# beaconboard3.net
KiCad netlist of a schematic drawn in EAGLE
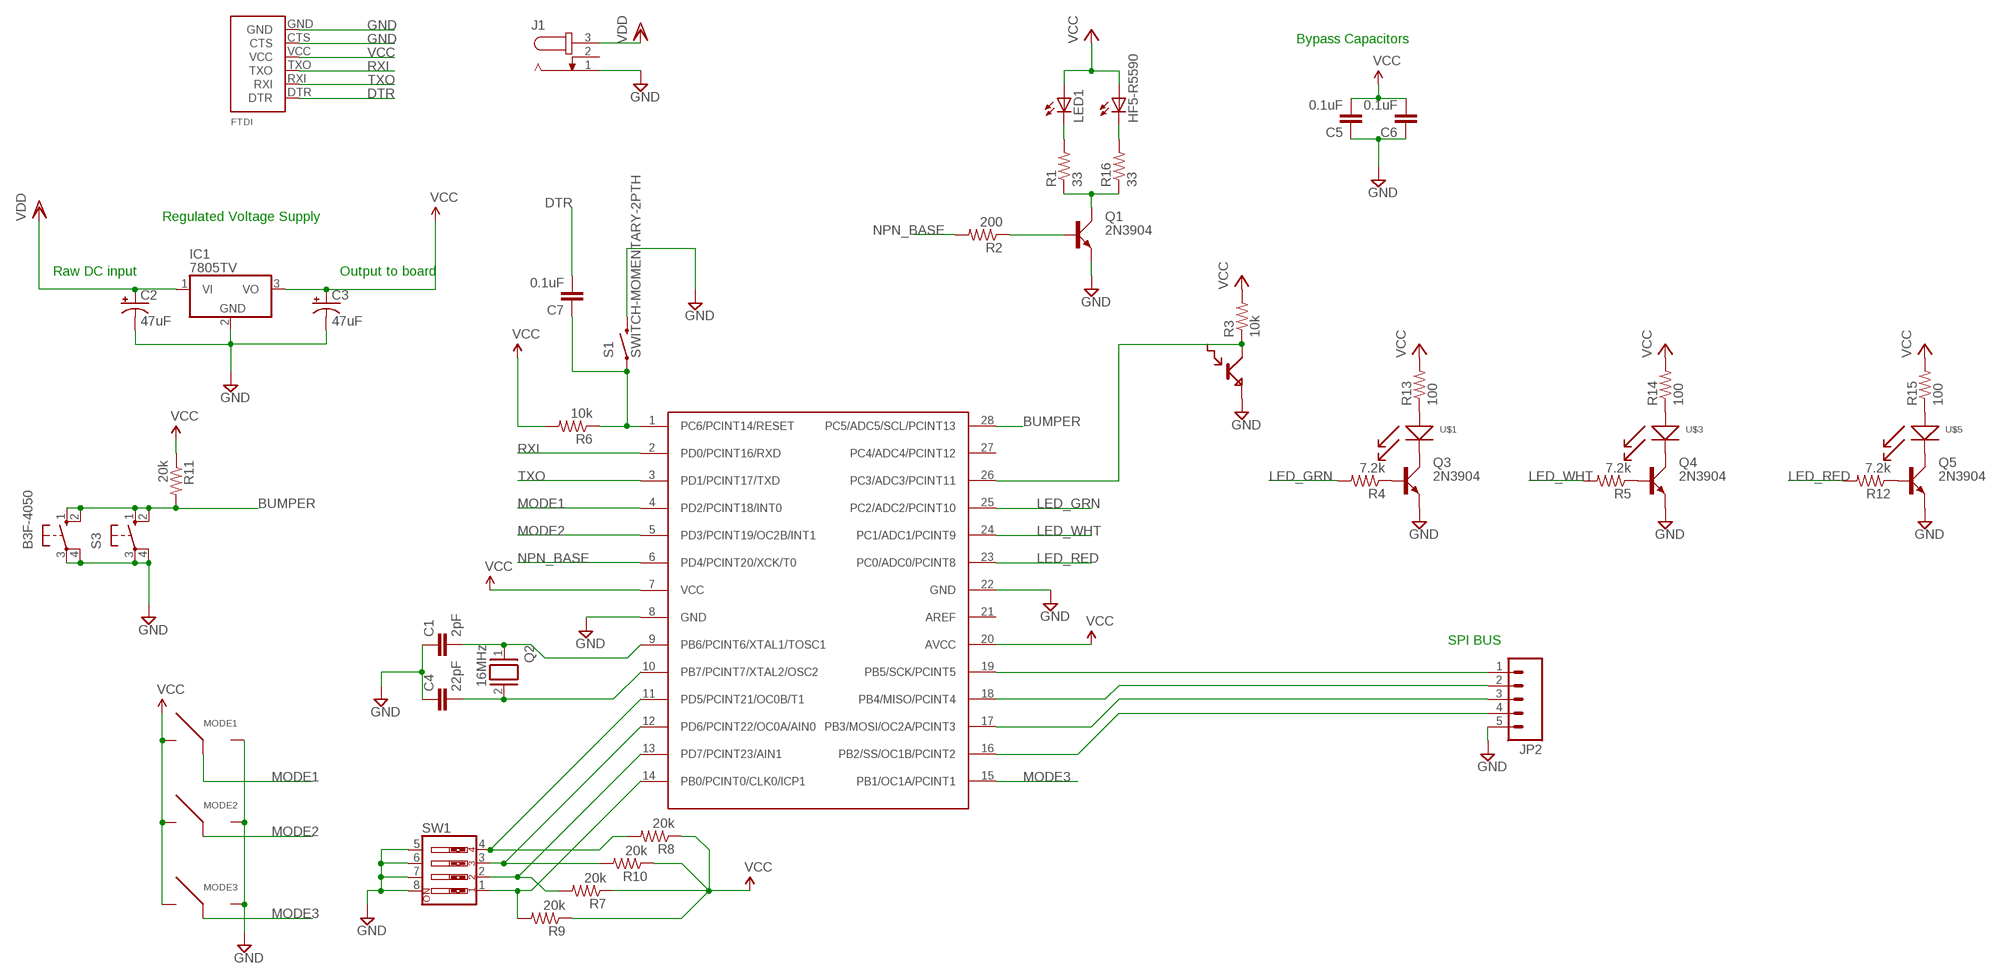
[diagram p0: schematic, sheet 1]

(export (version "E")
  (design (tool "Eeschema 10.0.6"))
  (components
    (comp (ref "B3F-4050")
      (value "40-XX")
      (footprint "eagle-import:B3F-40XX")
      (fields (field (name "MF") "OMRON COMPONENTS USA") (field (name "MPN") "B3F-4000"))
      (libsource (lib "eagle-import") (part "40-XX"))
    )
    (comp (ref "C1")
      (value "2pF")
      (footprint "eagle-import:CAP-PTH-SMALL")
      (libsource (lib "eagle-import") (part "CAPPTH"))
    )
    (comp (ref "C2")
      (value "47uF")
      (footprint "eagle-import:CPOL-RADIAL-10UF-25V")
      (libsource (lib "eagle-import") (part "CAP_POLPTH2"))
    )
    (comp (ref "C3")
      (value "47uF")
      (footprint "eagle-import:CPOL-RADIAL-10UF-25V")
      (libsource (lib "eagle-import") (part "CAP_POLPTH2"))
    )
    (comp (ref "C4")
      (value "22pF")
      (footprint "eagle-import:CAP-PTH-SMALL")
      (libsource (lib "eagle-import") (part "CAPPTH"))
    )
    (comp (ref "C5")
      (value "0.1uF")
      (footprint "eagle-import:CAP-PTH-5MM")
      (libsource (lib "eagle-import") (part "CAPPTH1"))
    )
    (comp (ref "C6")
      (value "0.1uF")
      (footprint "eagle-import:CAP-PTH-5MM")
      (libsource (lib "eagle-import") (part "CAPPTH1"))
    )
    (comp (ref "C7")
      (value "0.1uF")
      (footprint "eagle-import:CAP-PTH-5MM")
      (libsource (lib "eagle-import") (part "CAPPTH1"))
    )
    (comp (ref "HF5-R5590")
      (value "LED-2AC-CP41B-WES")
      (footprint "eagle-import:CP41B")
      (libsource (lib "eagle-import") (part "LED-2AC-CP41B-WES"))
    )
    (comp (ref "IC1")
      (value "7805TV")
      (footprint "eagle-import:TO220V")
      (libsource (lib "eagle-import") (part "78TV05"))
    )
    (comp (ref "J1")
      (value "JACK-PLUG1")
      (footprint "eagle-import:SPC4078")
      (libsource (lib "eagle-import") (part "JACK-PLUG1"))
    )
    (comp (ref "JP2")
      (value "M05LOCK_LONGPADS")
      (footprint "eagle-import:1X05_LOCK_LONGPADS")
      (libsource (lib "eagle-import") (part "M05LOCK_LONGPADS"))
    )
    (comp (ref "LED1")
      (value "LED-2AC-CP41B-WES")
      (footprint "eagle-import:CP41B")
      (libsource (lib "eagle-import") (part "LED-2AC-CP41B-WES"))
    )
    (comp (ref "MODE1")
      (value "SPD_SLIDE_SWITCH")
      (footprint "eagle-import:SPDT_SLIDE_SWITCH")
      (libsource (lib "eagle-import") (part "SPD_SLIDE_SWITCH"))
    )
    (comp (ref "MODE2")
      (value "SPD_SLIDE_SWITCH")
      (footprint "eagle-import:SPDT_SLIDE_SWITCH")
      (libsource (lib "eagle-import") (part "SPD_SLIDE_SWITCH"))
    )
    (comp (ref "MODE3")
      (value "SPD_SLIDE_SWITCH")
      (footprint "eagle-import:SPDT_SLIDE_SWITCH")
      (libsource (lib "eagle-import") (part "SPD_SLIDE_SWITCH"))
    )
    (comp (ref "Q1")
      (value "2N3904")
      (footprint "eagle-import:TO92D")
      (libsource (lib "eagle-import") (part "2N3904"))
    )
    (comp (ref "Q2")
      (value "16MHz")
      (footprint "eagle-import:QS")
      (libsource (lib "eagle-import") (part "XTAL/S"))
    )
    (comp (ref "Q3")
      (value "2N3904")
      (footprint "eagle-import:TO92D")
      (libsource (lib "eagle-import") (part "2N3904"))
    )
    (comp (ref "Q4")
      (value "2N3904")
      (footprint "eagle-import:TO92D")
      (libsource (lib "eagle-import") (part "2N3904"))
    )
    (comp (ref "Q5")
      (value "2N3904")
      (footprint "eagle-import:TO92D")
      (libsource (lib "eagle-import") (part "2N3904"))
    )
    (comp (ref "R1")
      (value "33")
      (footprint "eagle-import:AXIAL-0.4")
      (libsource (lib "eagle-import") (part "RESISTORPTH-1/4W"))
    )
    (comp (ref "R2")
      (value "200")
      (footprint "eagle-import:AXIAL-0.4")
      (libsource (lib "eagle-import") (part "RESISTORPTH-1/4W"))
    )
    (comp (ref "R3")
      (value "10k")
      (footprint "eagle-import:AXIAL-0.4")
      (libsource (lib "eagle-import") (part "RESISTORPTH-1/4W"))
    )
    (comp (ref "R4")
      (value "7.2k")
      (footprint "eagle-import:AXIAL-0.4")
      (libsource (lib "eagle-import") (part "RESISTORPTH-1/4W"))
    )
    (comp (ref "R5")
      (value "7.2k")
      (footprint "eagle-import:AXIAL-0.4")
      (libsource (lib "eagle-import") (part "RESISTORPTH-1/4W"))
    )
    (comp (ref "R6")
      (value "10k")
      (footprint "eagle-import:AXIAL-0.4")
      (libsource (lib "eagle-import") (part "RESISTORPTH-1/4W"))
    )
    (comp (ref "R7")
      (value "20k")
      (footprint "eagle-import:AXIAL-0.4")
      (libsource (lib "eagle-import") (part "RESISTORPTH-1/4W"))
    )
    (comp (ref "R8")
      (value "20k")
      (footprint "eagle-import:AXIAL-0.4")
      (libsource (lib "eagle-import") (part "RESISTORPTH-1/4W"))
    )
    (comp (ref "R9")
      (value "20k")
      (footprint "eagle-import:AXIAL-0.4")
      (libsource (lib "eagle-import") (part "RESISTORPTH-1/4W"))
    )
    (comp (ref "R10")
      (value "20k")
      (footprint "eagle-import:AXIAL-0.4")
      (libsource (lib "eagle-import") (part "RESISTORPTH-1/4W"))
    )
    (comp (ref "R11")
      (value "20k")
      (footprint "eagle-import:AXIAL-0.4")
      (libsource (lib "eagle-import") (part "RESISTORPTH-1/4W"))
    )
    (comp (ref "R12")
      (value "7.2k")
      (footprint "eagle-import:AXIAL-0.4")
      (libsource (lib "eagle-import") (part "RESISTORPTH-1/4W"))
    )
    (comp (ref "R13")
      (value "100")
      (footprint "eagle-import:AXIAL-0.4")
      (libsource (lib "eagle-import") (part "RESISTORPTH-1/4W"))
    )
    (comp (ref "R14")
      (value "100")
      (footprint "eagle-import:AXIAL-0.4")
      (libsource (lib "eagle-import") (part "RESISTORPTH-1/4W"))
    )
    (comp (ref "R15")
      (value "100")
      (footprint "eagle-import:AXIAL-0.4")
      (libsource (lib "eagle-import") (part "RESISTORPTH-1/4W"))
    )
    (comp (ref "R16")
      (value "33")
      (footprint "eagle-import:AXIAL-0.4")
      (libsource (lib "eagle-import") (part "RESISTORPTH-1/4W"))
    )
    (comp (ref "S1")
      (value "SWITCH-MOMENTARY-2PTH")
      (footprint "eagle-import:TACTILE-PTH")
      (libsource (lib "eagle-import") (part "SWITCH-MOMENTARY-2PTH"))
    )
    (comp (ref "S3")
      (value "40-XX")
      (footprint "eagle-import:B3F-40XX")
      (fields (field (name "MF") "OMRON COMPONENTS USA") (field (name "MPN") "B3F-4000"))
      (libsource (lib "eagle-import") (part "40-XX"))
    )
    (comp (ref "SW1")
      (value "SW_DIP-4")
      (footprint "eagle-import:EDG-04")
      (libsource (lib "eagle-import") (part "SW_DIP-4"))
    )
    (comp (ref "U$1")
      (value "8MM_LED")
      (footprint "eagle-import:8MM_LED")
      (libsource (lib "eagle-import") (part "8MM_LED"))
    )
    (comp (ref "U$2")
      (value "BPW77NA")
      (footprint "eagle-import:TO-18")
      (libsource (lib "eagle-import") (part "BPW77NA"))
    )
    (comp (ref "U$3")
      (value "8MM_LED")
      (footprint "eagle-import:8MM_LED")
      (libsource (lib "eagle-import") (part "8MM_LED"))
    )
    (comp (ref "U$4")
      (value "ATMEGA328")
      (footprint "eagle-import:DIL28-3")
      (libsource (lib "eagle-import") (part "ATMEGA328"))
    )
    (comp (ref "U$5")
      (value "8MM_LED")
      (footprint "eagle-import:8MM_LED")
      (libsource (lib "eagle-import") (part "8MM_LED"))
    )
    (comp (ref "U$6")
      (value "FTDI")
      (footprint "eagle-import:FTDI")
      (libsource (lib "eagle-import") (part "FTDI"))
    )
  )
  (nets
    (net (code "1") (name "/BUMPER") (class "Default")
      (node (ref "B3F-4050") (pin "1") (pinfunction "S_1") (pintype "passive"))
      (node (ref "B3F-4050") (pin "2") (pinfunction "S1_2") (pintype "passive"))
      (node (ref "R11") (pin "P$2") (pinfunction "2_P$2") (pintype "passive"))
      (node (ref "S3") (pin "1") (pinfunction "S_1") (pintype "passive"))
      (node (ref "S3") (pin "2") (pinfunction "S1_2") (pintype "passive"))
      (node (ref "U$4") (pin "28") (pinfunction "PC5/ADC5/SCL/PCINT13_28") (pintype "bidirectional"))
    )
    (net (code "2") (name "/DTR") (class "Default")
      (node (ref "C7") (pin "2") (pinfunction "2_2") (pintype "passive"))
      (node (ref "U$6") (pin "DTR") (pinfunction "DTR_DTR") (pintype "bidirectional"))
    )
    (net (code "3") (name "/LED_GRN") (class "Default")
      (node (ref "R4") (pin "P$2") (pinfunction "2_P$2") (pintype "passive"))
      (node (ref "U$4") (pin "25") (pinfunction "PC2/ADC2/PCINT10_25") (pintype "bidirectional"))
    )
    (net (code "4") (name "/LED_RED") (class "Default")
      (node (ref "R12") (pin "P$2") (pinfunction "2_P$2") (pintype "passive"))
      (node (ref "U$4") (pin "23") (pinfunction "PC0/ADC0/PCINT8_23") (pintype "bidirectional"))
    )
    (net (code "5") (name "/LED_WHT") (class "Default")
      (node (ref "R5") (pin "P$2") (pinfunction "2_P$2") (pintype "passive"))
      (node (ref "U$4") (pin "24") (pinfunction "PC1/ADC1/PCINT9_24") (pintype "bidirectional"))
    )
    (net (code "6") (name "/MODE1") (class "Default")
      (node (ref "MODE1") (pin "2") (pinfunction "2_2") (pintype "bidirectional"))
      (node (ref "U$4") (pin "4") (pinfunction "PD2/PCINT18/INT0_4") (pintype "bidirectional"))
    )
    (net (code "7") (name "/MODE2") (class "Default")
      (node (ref "MODE2") (pin "2") (pinfunction "2_2") (pintype "bidirectional"))
      (node (ref "U$4") (pin "5") (pinfunction "PD3/PCINT19/OC2B/INT1_5") (pintype "bidirectional"))
    )
    (net (code "8") (name "/MODE3") (class "Default")
      (node (ref "MODE3") (pin "2") (pinfunction "2_2") (pintype "bidirectional"))
      (node (ref "U$4") (pin "15") (pinfunction "PB1/OC1A/PCINT1_15") (pintype "bidirectional"))
    )
    (net (code "9") (name "/NPN_BASE") (class "Default")
      (node (ref "R2") (pin "P$2") (pinfunction "2_P$2") (pintype "passive"))
      (node (ref "U$4") (pin "6") (pinfunction "PD4/PCINT20/XCK/T0_6") (pintype "bidirectional"))
    )
    (net (code "10") (name "/RXI") (class "Default")
      (node (ref "U$4") (pin "2") (pinfunction "PD0/PCINT16/RXD_2") (pintype "bidirectional"))
      (node (ref "U$6") (pin "TXO") (pinfunction "TXO_TXO") (pintype "bidirectional"))
    )
    (net (code "11") (name "/TXO") (class "Default")
      (node (ref "U$4") (pin "3") (pinfunction "PD1/PCINT17/TXD_3") (pintype "bidirectional"))
      (node (ref "U$6") (pin "RXI") (pinfunction "RXI_RXI") (pintype "bidirectional"))
    )
    (net (code "12") (name "GND") (class "Default")
      (node (ref "B3F-4050") (pin "3") (pinfunction "P_3") (pintype "passive"))
      (node (ref "B3F-4050") (pin "4") (pinfunction "P1_4") (pintype "passive"))
      (node (ref "C1") (pin "1") (pinfunction "1_1") (pintype "passive"))
      (node (ref "C2") (pin "2") (pinfunction "-_2") (pintype "passive"))
      (node (ref "C3") (pin "2") (pinfunction "-_2") (pintype "passive"))
      (node (ref "C4") (pin "1") (pinfunction "1_1") (pintype "passive"))
      (node (ref "C5") (pin "1") (pinfunction "1_1") (pintype "passive"))
      (node (ref "C6") (pin "1") (pinfunction "1_1") (pintype "passive"))
      (node (ref "IC1") (pin "2") (pinfunction "GND_2") (pintype "passive"))
      (node (ref "J1") (pin "1") (pinfunction "1_1") (pintype "passive"))
      (node (ref "JP2") (pin "5") (pinfunction "5_5") (pintype "passive"))
      (node (ref "MODE1") (pin "3") (pinfunction "3_3") (pintype "bidirectional"))
      (node (ref "MODE2") (pin "3") (pinfunction "3_3") (pintype "bidirectional"))
      (node (ref "MODE3") (pin "3") (pinfunction "3_3") (pintype "bidirectional"))
      (node (ref "Q1") (pin "E") (pinfunction "E_E") (pintype "passive"))
      (node (ref "Q3") (pin "E") (pinfunction "E_E") (pintype "passive"))
      (node (ref "Q4") (pin "E") (pinfunction "E_E") (pintype "passive"))
      (node (ref "Q5") (pin "E") (pinfunction "E_E") (pintype "passive"))
      (node (ref "S1") (pin "3") (pinfunction "2_3") (pintype "passive"))
      (node (ref "S3") (pin "3") (pinfunction "P_3") (pintype "passive"))
      (node (ref "S3") (pin "4") (pinfunction "P1_4") (pintype "passive"))
      (node (ref "SW1") (pin "5") (pinfunction "5_5") (pintype "passive"))
      (node (ref "SW1") (pin "6") (pinfunction "6_6") (pintype "passive"))
      (node (ref "SW1") (pin "7") (pinfunction "7_7") (pintype "passive"))
      (node (ref "SW1") (pin "8") (pinfunction "8_8") (pintype "passive"))
      (node (ref "U$2") (pin "E") (pinfunction "E_E") (pintype "bidirectional"))
      (node (ref "U$4") (pin "22") (pinfunction "GND_22") (pintype "power_in"))
      (node (ref "U$4") (pin "8") (pinfunction "GND_8") (pintype "power_in"))
      (node (ref "U$6") (pin "CTS") (pinfunction "CTS_CTS") (pintype "bidirectional"))
      (node (ref "U$6") (pin "GND") (pinfunction "GND_GND") (pintype "bidirectional"))
    )
    (net (code "13") (name "Net-(Q3-PadC)") (class "Default")
      (node (ref "Q3") (pin "C") (pinfunction "C_C") (pintype "passive"))
      (node (ref "U$1") (pin "NEG") (pinfunction "NEG_NEG") (pintype "bidirectional"))
    )
    (net (code "14") (name "Net-(Q4-PadC)") (class "Default")
      (node (ref "Q4") (pin "C") (pinfunction "C_C") (pintype "passive"))
      (node (ref "U$3") (pin "NEG") (pinfunction "NEG_NEG") (pintype "bidirectional"))
    )
    (net (code "15") (name "Net-(Q5-PadC)") (class "Default")
      (node (ref "Q5") (pin "C") (pinfunction "C_C") (pintype "passive"))
      (node (ref "U$5") (pin "NEG") (pinfunction "NEG_NEG") (pintype "bidirectional"))
    )
    (net (code "16") (name "Net-(R1-1)") (class "Default")
      (node (ref "Q1") (pin "C") (pinfunction "C_C") (pintype "passive"))
      (node (ref "R1") (pin "P$1") (pinfunction "1_P$1") (pintype "passive"))
      (node (ref "R16") (pin "P$1") (pinfunction "1_P$1") (pintype "passive"))
    )
    (net (code "17") (name "Net-(R1-2)") (class "Default")
      (node (ref "LED1") (pin "1") (pinfunction "C_1") (pintype "passive"))
      (node (ref "LED1") (pin "4") (pinfunction "C_4") (pintype "passive"))
      (node (ref "R1") (pin "P$2") (pinfunction "2_P$2") (pintype "passive"))
    )
    (net (code "18") (name "Net-(R2-1)") (class "Default")
      (node (ref "Q1") (pin "B") (pinfunction "B_B") (pintype "passive"))
      (node (ref "R2") (pin "P$1") (pinfunction "1_P$1") (pintype "passive"))
    )
    (net (code "19") (name "Net-(R3-1)") (class "Default")
      (node (ref "R3") (pin "P$1") (pinfunction "1_P$1") (pintype "passive"))
      (node (ref "U$2") (pin "C") (pinfunction "C_C") (pintype "bidirectional"))
      (node (ref "U$4") (pin "26") (pinfunction "PC3/ADC3/PCINT11_26") (pintype "bidirectional"))
    )
    (net (code "20") (name "Net-(R4-1)") (class "Default")
      (node (ref "Q3") (pin "B") (pinfunction "B_B") (pintype "passive"))
      (node (ref "R4") (pin "P$1") (pinfunction "1_P$1") (pintype "passive"))
    )
    (net (code "21") (name "Net-(R5-1)") (class "Default")
      (node (ref "Q4") (pin "B") (pinfunction "B_B") (pintype "passive"))
      (node (ref "R5") (pin "P$1") (pinfunction "1_P$1") (pintype "passive"))
    )
    (net (code "22") (name "Net-(R6-1)") (class "Default")
      (node (ref "C7") (pin "1") (pinfunction "1_1") (pintype "passive"))
      (node (ref "R6") (pin "P$1") (pinfunction "1_P$1") (pintype "passive"))
      (node (ref "S1") (pin "1") (pinfunction "1_1") (pintype "passive"))
      (node (ref "U$4") (pin "1") (pinfunction "PC6/PCINT14/RESET_1") (pintype "bidirectional"))
    )
    (net (code "23") (name "Net-(R7-2)") (class "Default")
      (node (ref "R7") (pin "P$2") (pinfunction "2_P$2") (pintype "passive"))
      (node (ref "SW1") (pin "2") (pinfunction "2_2") (pintype "passive"))
      (node (ref "U$4") (pin "13") (pinfunction "PD7/PCINT23/AIN1_13") (pintype "bidirectional"))
    )
    (net (code "24") (name "Net-(R8-2)") (class "Default")
      (node (ref "R8") (pin "P$2") (pinfunction "2_P$2") (pintype "passive"))
      (node (ref "SW1") (pin "4") (pinfunction "4_4") (pintype "passive"))
      (node (ref "U$4") (pin "11") (pinfunction "PD5/PCINT21/OC0B/T1_11") (pintype "bidirectional"))
    )
    (net (code "25") (name "Net-(R9-2)") (class "Default")
      (node (ref "R9") (pin "P$2") (pinfunction "2_P$2") (pintype "passive"))
      (node (ref "SW1") (pin "1") (pinfunction "1_1") (pintype "passive"))
      (node (ref "U$4") (pin "14") (pinfunction "PB0/PCINT0/CLK0/ICP1_14") (pintype "bidirectional"))
    )
    (net (code "26") (name "Net-(R10-2)") (class "Default")
      (node (ref "R10") (pin "P$2") (pinfunction "2_P$2") (pintype "passive"))
      (node (ref "SW1") (pin "3") (pinfunction "3_3") (pintype "passive"))
      (node (ref "U$4") (pin "12") (pinfunction "PD6/PCINT22/OC0A/AIN0_12") (pintype "bidirectional"))
    )
    (net (code "27") (name "Net-(R12-1)") (class "Default")
      (node (ref "Q5") (pin "B") (pinfunction "B_B") (pintype "passive"))
      (node (ref "R12") (pin "P$1") (pinfunction "1_P$1") (pintype "passive"))
    )
    (net (code "28") (name "Net-(R13-1)") (class "Default")
      (node (ref "R13") (pin "P$1") (pinfunction "1_P$1") (pintype "passive"))
      (node (ref "U$1") (pin "POS") (pinfunction "POS_POS") (pintype "bidirectional"))
    )
    (net (code "29") (name "Net-(R14-1)") (class "Default")
      (node (ref "R14") (pin "P$1") (pinfunction "1_P$1") (pintype "passive"))
      (node (ref "U$3") (pin "POS") (pinfunction "POS_POS") (pintype "bidirectional"))
    )
    (net (code "30") (name "Net-(R15-1)") (class "Default")
      (node (ref "R15") (pin "P$1") (pinfunction "1_P$1") (pintype "passive"))
      (node (ref "U$5") (pin "POS") (pinfunction "POS_POS") (pintype "bidirectional"))
    )
    (net (code "31") (name "Net-(R16-2)") (class "Default")
      (node (ref "HF5-R5590") (pin "1") (pinfunction "C_1") (pintype "passive"))
      (node (ref "HF5-R5590") (pin "4") (pinfunction "C_4") (pintype "passive"))
      (node (ref "R16") (pin "P$2") (pinfunction "2_P$2") (pintype "passive"))
    )
    (net (code "32") (name "Net-(U$4-PB2{slash}SS{slash}OC1B{slash}PCINT2)") (class "Default")
      (node (ref "JP2") (pin "4") (pinfunction "4_4") (pintype "passive"))
      (node (ref "U$4") (pin "16") (pinfunction "PB2/SS/OC1B/PCINT2_16") (pintype "bidirectional"))
    )
    (net (code "33") (name "Net-(U$4-PB3{slash}MOSI{slash}OC2A{slash}PCINT3)") (class "Default")
      (node (ref "JP2") (pin "3") (pinfunction "3_3") (pintype "passive"))
      (node (ref "U$4") (pin "17") (pinfunction "PB3/MOSI/OC2A/PCINT3_17") (pintype "bidirectional"))
    )
    (net (code "34") (name "Net-(U$4-PB4{slash}MISO{slash}PCINT4)") (class "Default")
      (node (ref "JP2") (pin "2") (pinfunction "2_2") (pintype "passive"))
      (node (ref "U$4") (pin "18") (pinfunction "PB4/MISO/PCINT4_18") (pintype "bidirectional"))
    )
    (net (code "35") (name "Net-(U$4-PB5{slash}SCK{slash}PCINT5)") (class "Default")
      (node (ref "JP2") (pin "1") (pinfunction "1_1") (pintype "passive"))
      (node (ref "U$4") (pin "19") (pinfunction "PB5/SCK/PCINT5_19") (pintype "bidirectional"))
    )
    (net (code "36") (name "Net-(U$4-PB6{slash}PCINT6{slash}XTAL1{slash}TOSC1)") (class "Default")
      (node (ref "C1") (pin "2") (pinfunction "2_2") (pintype "passive"))
      (node (ref "Q2") (pin "1") (pinfunction "1_1") (pintype "passive"))
      (node (ref "U$4") (pin "9") (pinfunction "PB6/PCINT6/XTAL1/TOSC1_9") (pintype "bidirectional"))
    )
    (net (code "37") (name "Net-(U$4-PB7{slash}PCINT7{slash}XTAL2{slash}OSC2)") (class "Default")
      (node (ref "C4") (pin "2") (pinfunction "2_2") (pintype "passive"))
      (node (ref "Q2") (pin "2") (pinfunction "2_2") (pintype "passive"))
      (node (ref "U$4") (pin "10") (pinfunction "PB7/PCINT7/XTAL2/OSC2_10") (pintype "bidirectional"))
    )
    (net (code "38") (name "VCC") (class "Default")
      (node (ref "C3") (pin "1") (pinfunction "+_1") (pintype "passive"))
      (node (ref "C5") (pin "2") (pinfunction "2_2") (pintype "passive"))
      (node (ref "C6") (pin "2") (pinfunction "2_2") (pintype "passive"))
      (node (ref "HF5-R5590") (pin "2") (pinfunction "A_2") (pintype "passive"))
      (node (ref "HF5-R5590") (pin "3") (pinfunction "A_3") (pintype "passive"))
      (node (ref "IC1") (pin "3") (pinfunction "VO_3") (pintype "passive"))
      (node (ref "LED1") (pin "2") (pinfunction "A_2") (pintype "passive"))
      (node (ref "LED1") (pin "3") (pinfunction "A_3") (pintype "passive"))
      (node (ref "MODE1") (pin "1") (pinfunction "1_1") (pintype "bidirectional"))
      (node (ref "MODE2") (pin "1") (pinfunction "1_1") (pintype "bidirectional"))
      (node (ref "MODE3") (pin "1") (pinfunction "1_1") (pintype "bidirectional"))
      (node (ref "R10") (pin "P$1") (pinfunction "1_P$1") (pintype "passive"))
      (node (ref "R11") (pin "P$1") (pinfunction "1_P$1") (pintype "passive"))
      (node (ref "R13") (pin "P$2") (pinfunction "2_P$2") (pintype "passive"))
      (node (ref "R14") (pin "P$2") (pinfunction "2_P$2") (pintype "passive"))
      (node (ref "R15") (pin "P$2") (pinfunction "2_P$2") (pintype "passive"))
      (node (ref "R3") (pin "P$2") (pinfunction "2_P$2") (pintype "passive"))
      (node (ref "R6") (pin "P$2") (pinfunction "2_P$2") (pintype "passive"))
      (node (ref "R7") (pin "P$1") (pinfunction "1_P$1") (pintype "passive"))
      (node (ref "R8") (pin "P$1") (pinfunction "1_P$1") (pintype "passive"))
      (node (ref "R9") (pin "P$1") (pinfunction "1_P$1") (pintype "passive"))
      (node (ref "U$4") (pin "20") (pinfunction "AVCC_20") (pintype "bidirectional"))
      (node (ref "U$4") (pin "7") (pinfunction "VCC_7") (pintype "power_in"))
      (node (ref "U$6") (pin "VCC") (pinfunction "VCC_VCC") (pintype "bidirectional"))
    )
    (net (code "39") (name "VDD") (class "Default")
      (node (ref "C2") (pin "1") (pinfunction "+_1") (pintype "passive"))
      (node (ref "IC1") (pin "1") (pinfunction "VI_1") (pintype "input"))
      (node (ref "J1") (pin "3") (pinfunction "3_3") (pintype "passive"))
    )
    (net (code "40") (name "unconnected-(J1-Pad2)") (class "Default")
      (node (ref "J1") (pin "2") (pinfunction "2_2") (pintype "passive"))
    )
    (net (code "41") (name "unconnected-(U$4-AREF-Pad21)") (class "Default")
      (node (ref "U$4") (pin "21") (pinfunction "AREF_21") (pintype "bidirectional"))
    )
    (net (code "42") (name "unconnected-(U$4-PC4{slash}ADC4{slash}PCINT12-Pad27)") (class "Default")
      (node (ref "U$4") (pin "27") (pinfunction "PC4/ADC4/PCINT12_27") (pintype "bidirectional"))
    )
  )
)
